# Sheet1.net
KiCad netlist of a schematic drawn in Altium Designer
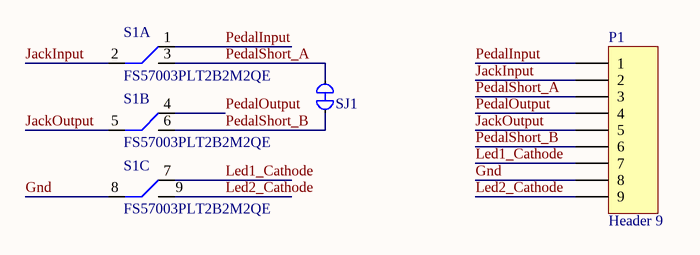
[diagram p0: Sheet1.SchDoc]

(export (version "E")
  (design (tool "Eeschema 10.0.6"))
  (components
    (comp (ref "P1")
      (value "Header 9")
      (footprint "HDR1X9_2.54")
      (description "Header, 9-Pin")
      (fields (field (name "PUBLISHER") "Altium Limited"))
      (libsource (lib "CustomLib") (part "Header 9"))
    )
    (comp (ref "S1")
      (value "FS57003PLT2B2M2QE")
      (footprint "SW_FS57003PLT2B2M2QE")
      (description "Mechanical 3PDT Footswitch")
      (libsource (lib "CustomLib") (part "FS57003PLT2B2M2QE"))
    )
    (comp (ref "SJ1")
      (value "Solder Jumper Shorted")
      (footprint "SOLDER_JUMPER_SHORTED")
      (libsource (lib "CustomLib") (part "Solder Jumper Shorted"))
    )
  )
  (nets
    (net (code "1") (name "/Gnd") (class "Default")
      (node (ref "P1") (pin "8") (pinfunction "8_8") (pintype "passive"))
      (node (ref "S1") (pin "8") (pinfunction "8_8") (pintype "passive"))
    )
    (net (code "2") (name "/JackInput") (class "Default")
      (node (ref "P1") (pin "2") (pinfunction "2_2") (pintype "passive"))
      (node (ref "S1") (pin "2") (pinfunction "2_2") (pintype "passive"))
    )
    (net (code "3") (name "/JackOutput") (class "Default")
      (node (ref "P1") (pin "5") (pinfunction "5_5") (pintype "passive"))
      (node (ref "S1") (pin "5") (pinfunction "5_5") (pintype "passive"))
    )
    (net (code "4") (name "/Led1_Cathode") (class "Default")
      (node (ref "P1") (pin "7") (pinfunction "7_7") (pintype "passive"))
      (node (ref "S1") (pin "7") (pinfunction "7_7") (pintype "passive"))
    )
    (net (code "5") (name "/Led2_Cathode") (class "Default")
      (node (ref "P1") (pin "9") (pinfunction "9_9") (pintype "passive"))
      (node (ref "S1") (pin "9") (pinfunction "9_9") (pintype "passive"))
    )
    (net (code "6") (name "/PedalInput") (class "Default")
      (node (ref "P1") (pin "1") (pinfunction "1_1") (pintype "passive"))
      (node (ref "S1") (pin "1") (pinfunction "1_1") (pintype "passive"))
    )
    (net (code "7") (name "/PedalOutput") (class "Default")
      (node (ref "P1") (pin "4") (pinfunction "4_4") (pintype "passive"))
      (node (ref "S1") (pin "4") (pinfunction "4_4") (pintype "passive"))
    )
    (net (code "8") (name "/PedalShort_A") (class "Default")
      (node (ref "P1") (pin "3") (pinfunction "3_3") (pintype "passive"))
      (node (ref "S1") (pin "3") (pinfunction "3_3") (pintype "passive"))
      (node (ref "SJ1") (pin "2") (pinfunction "2_2") (pintype "passive"))
    )
    (net (code "9") (name "/PedalShort_B") (class "Default")
      (node (ref "P1") (pin "6") (pinfunction "6_6") (pintype "passive"))
      (node (ref "S1") (pin "6") (pinfunction "6_6") (pintype "passive"))
      (node (ref "SJ1") (pin "1") (pinfunction "1_1") (pintype "passive"))
    )
  )
)
